# compashin_izzonu_fine.net
KiCad netlist of a schematic drawn in EAGLE
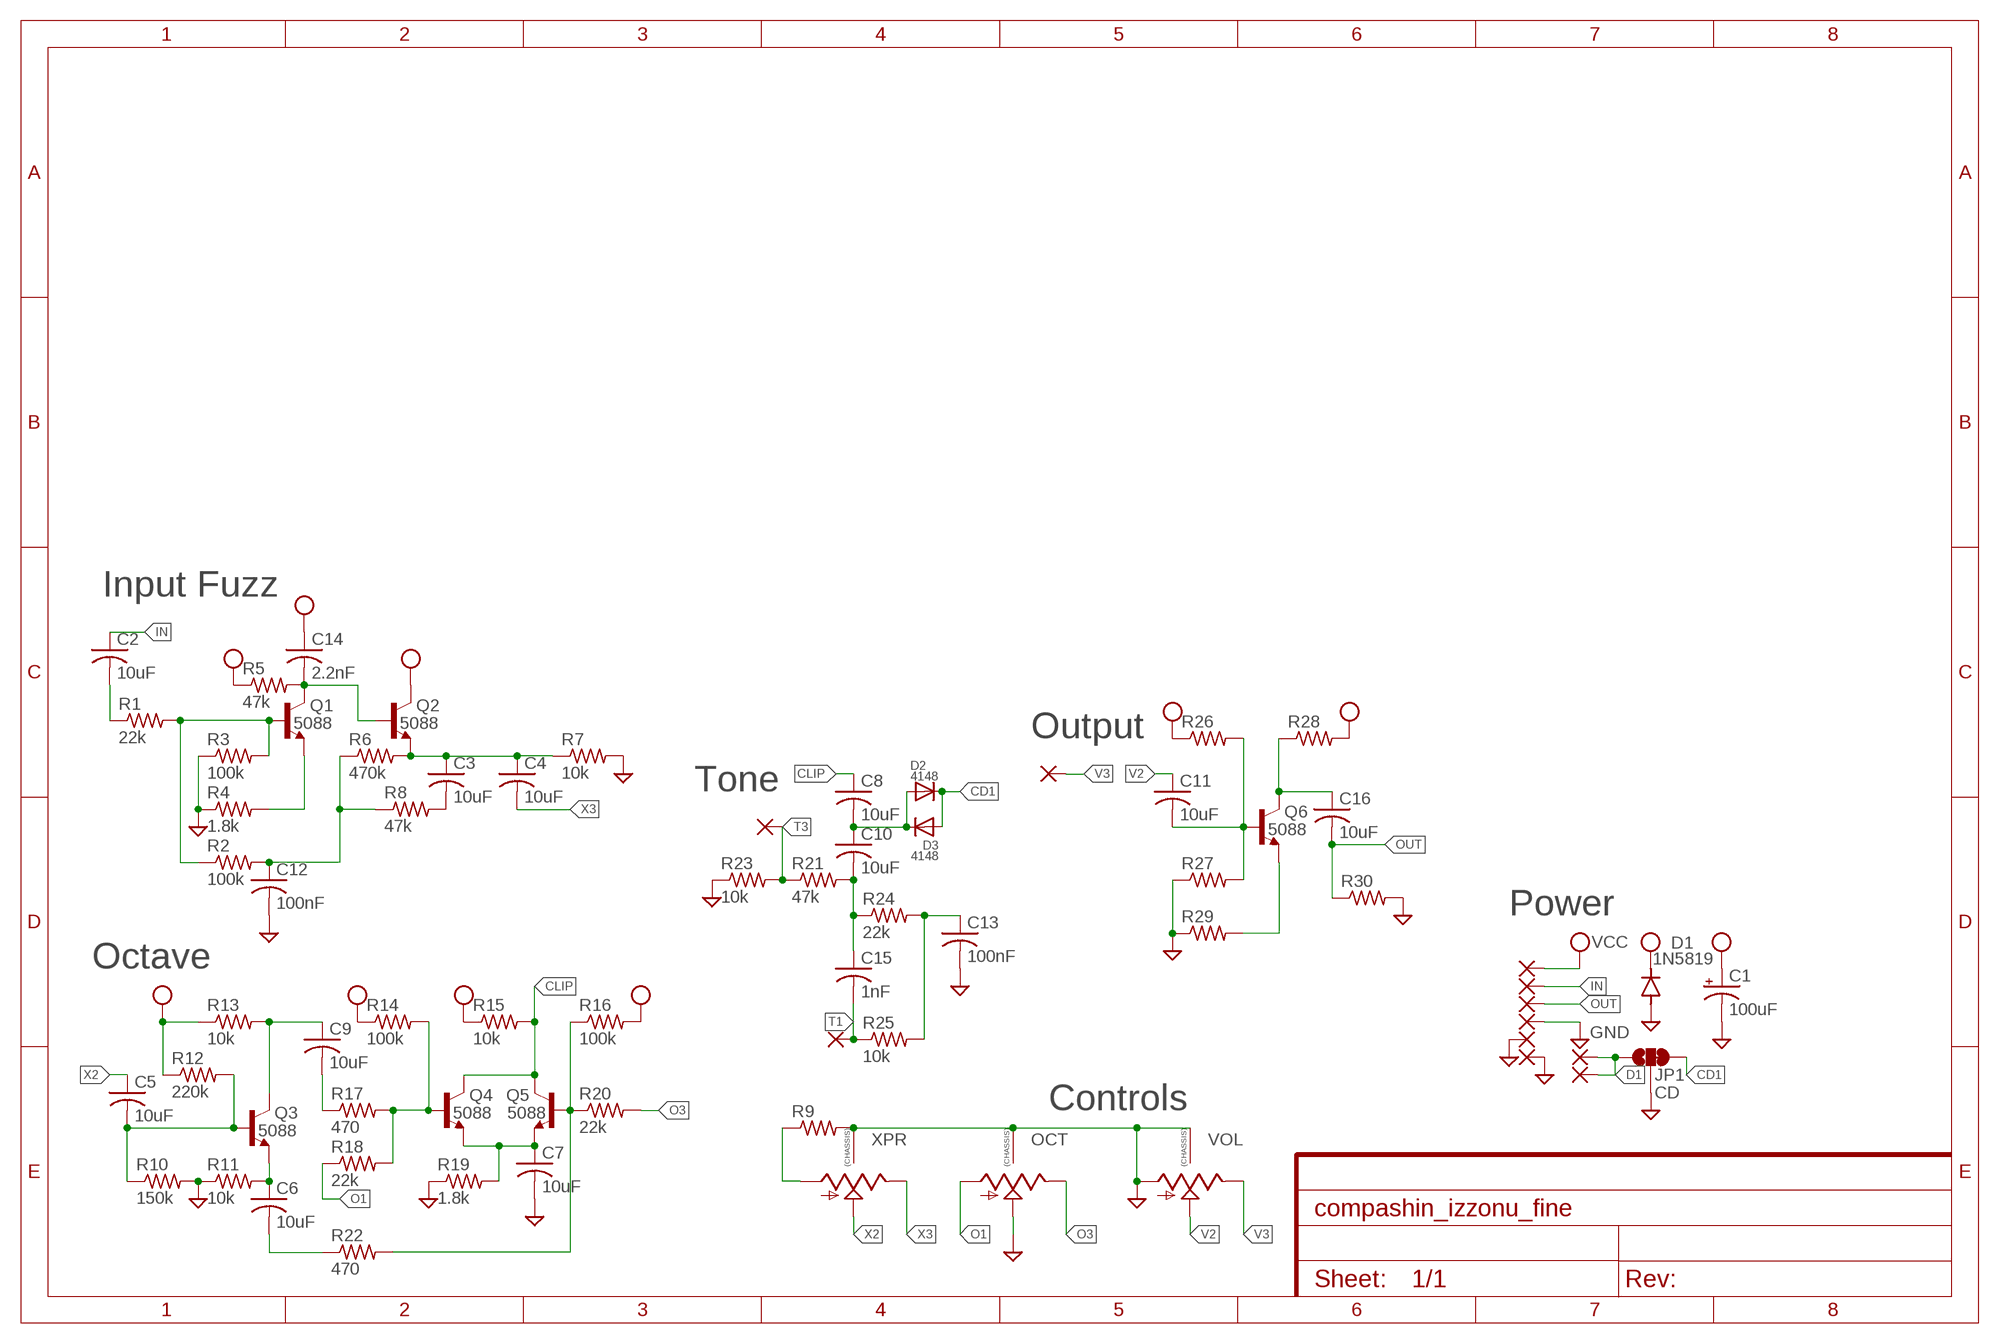
[diagram p0: schematic, sheet 1]

(export (version "E")
  (design (tool "Eeschema 10.0.6"))
  (components
    (comp (ref "C1")
      (value "100uF")
      (footprint "eagle-import:CPOL-RADIAL-2.5MM-6.5MM")
      (libsource (lib "eagle-import") (part "100UF-POLAR-RADIAL-2.5MM-25V-20%"))
    )
    (comp (ref "C2")
      (value "10uF")
      (footprint "eagle-import:C0805")
      (libsource (lib "eagle-import") (part "C-USC0805"))
    )
    (comp (ref "C3")
      (value "10uF")
      (footprint "eagle-import:C0805")
      (libsource (lib "eagle-import") (part "C-USC0805"))
    )
    (comp (ref "C4")
      (value "10uF")
      (footprint "eagle-import:C0805")
      (libsource (lib "eagle-import") (part "C-USC0805"))
    )
    (comp (ref "C5")
      (value "10uF")
      (footprint "eagle-import:C0805")
      (libsource (lib "eagle-import") (part "C-USC0805"))
    )
    (comp (ref "C6")
      (value "10uF")
      (footprint "eagle-import:C0805")
      (libsource (lib "eagle-import") (part "C-USC0805"))
    )
    (comp (ref "C7")
      (value "10uF")
      (footprint "eagle-import:C0805")
      (libsource (lib "eagle-import") (part "C-USC0805"))
    )
    (comp (ref "C8")
      (value "10uF")
      (footprint "eagle-import:C0805")
      (libsource (lib "eagle-import") (part "C-USC0805"))
    )
    (comp (ref "C9")
      (value "10uF")
      (footprint "eagle-import:C0805")
      (libsource (lib "eagle-import") (part "C-USC0805"))
    )
    (comp (ref "C10")
      (value "10uF")
      (footprint "eagle-import:C0805")
      (libsource (lib "eagle-import") (part "C-USC0805"))
    )
    (comp (ref "C11")
      (value "10uF")
      (footprint "eagle-import:C0805")
      (libsource (lib "eagle-import") (part "C-USC0805"))
    )
    (comp (ref "C12")
      (value "100nF")
      (footprint "eagle-import:C0402")
      (libsource (lib "eagle-import") (part "C-USC0402"))
    )
    (comp (ref "C13")
      (value "100nF")
      (footprint "eagle-import:C0402")
      (libsource (lib "eagle-import") (part "C-USC0402"))
    )
    (comp (ref "C14")
      (value "2.2nF")
      (footprint "eagle-import:C0402")
      (libsource (lib "eagle-import") (part "C-USC0402"))
    )
    (comp (ref "C15")
      (value "1nF")
      (footprint "eagle-import:C0402")
      (libsource (lib "eagle-import") (part "C-USC0402"))
    )
    (comp (ref "C16")
      (value "10uF")
      (footprint "eagle-import:C0805")
      (libsource (lib "eagle-import") (part "C-USC0805"))
    )
    (comp (ref "D1")
      (value "1N5819")
      (footprint "eagle-import:SOD123")
      (libsource (lib "eagle-import") (part "DIODE-SOD123"))
    )
    (comp (ref "D2")
      (value "4148")
      (footprint "eagle-import:SOD-123")
      (libsource (lib "eagle-import") (part "DIODESOD-123"))
    )
    (comp (ref "D3")
      (value "4148")
      (footprint "eagle-import:SOD-123")
      (libsource (lib "eagle-import") (part "DIODESOD-123"))
    )
    (comp (ref "JP1")
      (value "CD")
      (footprint "eagle-import:SMT-JUMPER_3_1-NC_TRACE_SILK")
      (libsource (lib "eagle-import") (part "JUMPER-SMT_3_1-NC_TRACE_SILK"))
    )
    (comp (ref "OCT")
      (value "9MM_SNAP-IN_POT_CHASSIS")
      (footprint "eagle-import:9MM_SNAP-IN_POT")
      (libsource (lib "eagle-import") (part "9MM_SNAP-IN_POT_CHASSIS"))
    )
    (comp (ref "PAD1")
      (value "1,6/0,8")
      (footprint "eagle-import:1,6_0,8")
      (libsource (lib "eagle-import") (part "1,6/0,8"))
    )
    (comp (ref "PAD2")
      (value "1,6/0,8")
      (footprint "eagle-import:1,6_0,8")
      (libsource (lib "eagle-import") (part "1,6/0,8"))
    )
    (comp (ref "PAD3")
      (value "1,6/0,8")
      (footprint "eagle-import:1,6_0,8")
      (libsource (lib "eagle-import") (part "1,6/0,8"))
    )
    (comp (ref "PAD4")
      (value "1,6/0,8")
      (footprint "eagle-import:1,6_0,8")
      (libsource (lib "eagle-import") (part "1,6/0,8"))
    )
    (comp (ref "PAD5")
      (value "1,6/0,8")
      (footprint "eagle-import:1,6_0,8")
      (libsource (lib "eagle-import") (part "1,6/0,8"))
    )
    (comp (ref "PAD6")
      (value "1,6/0,8")
      (footprint "eagle-import:1,6_0,8")
      (libsource (lib "eagle-import") (part "1,6/0,8"))
    )
    (comp (ref "PAD7")
      (value "1,6/0,8")
      (footprint "eagle-import:1,6_0,8")
      (libsource (lib "eagle-import") (part "1,6/0,8"))
    )
    (comp (ref "PAD8")
      (value "1,6/0,8")
      (footprint "eagle-import:1,6_0,8")
      (libsource (lib "eagle-import") (part "1,6/0,8"))
    )
    (comp (ref "Q1")
      (value "5088")
      (footprint "eagle-import:SOT23-BEC")
      (fields (field (name "MF") "ON Semiconductor") (field (name "MP") "MMBT5088"))
      (libsource (lib "eagle-import") (part "MMBT5088"))
    )
    (comp (ref "Q2")
      (value "5088")
      (footprint "eagle-import:SOT23-BEC")
      (fields (field (name "MF") "ON Semiconductor") (field (name "MP") "MMBT5088"))
      (libsource (lib "eagle-import") (part "MMBT5088"))
    )
    (comp (ref "Q3")
      (value "5088")
      (footprint "eagle-import:SOT23-BEC")
      (fields (field (name "MF") "ON Semiconductor") (field (name "MP") "MMBT5088"))
      (libsource (lib "eagle-import") (part "MMBT5088"))
    )
    (comp (ref "Q4")
      (value "5088")
      (footprint "eagle-import:SOT23-BEC")
      (fields (field (name "MF") "ON Semiconductor") (field (name "MP") "MMBT5088"))
      (libsource (lib "eagle-import") (part "MMBT5088"))
    )
    (comp (ref "Q5")
      (value "5088")
      (footprint "eagle-import:SOT23-BEC")
      (fields (field (name "MF") "ON Semiconductor") (field (name "MP") "MMBT5088"))
      (libsource (lib "eagle-import") (part "MMBT5088"))
    )
    (comp (ref "Q6")
      (value "5088")
      (footprint "eagle-import:SOT23-BEC")
      (fields (field (name "MF") "ON Semiconductor") (field (name "MP") "MMBT5088"))
      (libsource (lib "eagle-import") (part "MMBT5088"))
    )
    (comp (ref "R1")
      (value "22k")
      (footprint "eagle-import:R0402")
      (libsource (lib "eagle-import") (part "R-US_R0402"))
    )
    (comp (ref "R2")
      (value "100k")
      (footprint "eagle-import:R0402")
      (libsource (lib "eagle-import") (part "R-US_R0402"))
    )
    (comp (ref "R3")
      (value "100k")
      (footprint "eagle-import:R0402")
      (libsource (lib "eagle-import") (part "R-US_R0402"))
    )
    (comp (ref "R4")
      (value "1.8k")
      (footprint "eagle-import:R0402")
      (libsource (lib "eagle-import") (part "R-US_R0402"))
    )
    (comp (ref "R5")
      (value "47k")
      (footprint "eagle-import:R0402")
      (libsource (lib "eagle-import") (part "R-US_R0402"))
    )
    (comp (ref "R6")
      (value "470k")
      (footprint "eagle-import:R0402")
      (libsource (lib "eagle-import") (part "R-US_R0402"))
    )
    (comp (ref "R7")
      (value "10k")
      (footprint "eagle-import:R0402")
      (libsource (lib "eagle-import") (part "R-US_R0402"))
    )
    (comp (ref "R8")
      (value "47k")
      (footprint "eagle-import:R0402")
      (libsource (lib "eagle-import") (part "R-US_R0402"))
    )
    (comp (ref "R9")
      (value "R-US_R0402")
      (footprint "eagle-import:R0402")
      (libsource (lib "eagle-import") (part "R-US_R0402"))
    )
    (comp (ref "R10")
      (value "150k")
      (footprint "eagle-import:R0402")
      (libsource (lib "eagle-import") (part "R-US_R0402"))
    )
    (comp (ref "R11")
      (value "10k")
      (footprint "eagle-import:R0402")
      (libsource (lib "eagle-import") (part "R-US_R0402"))
    )
    (comp (ref "R12")
      (value "220k")
      (footprint "eagle-import:R0402")
      (libsource (lib "eagle-import") (part "R-US_R0402"))
    )
    (comp (ref "R13")
      (value "10k")
      (footprint "eagle-import:R0402")
      (libsource (lib "eagle-import") (part "R-US_R0402"))
    )
    (comp (ref "R14")
      (value "100k")
      (footprint "eagle-import:R0402")
      (libsource (lib "eagle-import") (part "R-US_R0402"))
    )
    (comp (ref "R15")
      (value "10k")
      (footprint "eagle-import:R0402")
      (libsource (lib "eagle-import") (part "R-US_R0402"))
    )
    (comp (ref "R16")
      (value "100k")
      (footprint "eagle-import:R0402")
      (libsource (lib "eagle-import") (part "R-US_R0402"))
    )
    (comp (ref "R17")
      (value "470")
      (footprint "eagle-import:R0402")
      (libsource (lib "eagle-import") (part "R-US_R0402"))
    )
    (comp (ref "R18")
      (value "22k")
      (footprint "eagle-import:R0402")
      (libsource (lib "eagle-import") (part "R-US_R0402"))
    )
    (comp (ref "R19")
      (value "1.8k")
      (footprint "eagle-import:R0402")
      (libsource (lib "eagle-import") (part "R-US_R0402"))
    )
    (comp (ref "R20")
      (value "22k")
      (footprint "eagle-import:R0402")
      (libsource (lib "eagle-import") (part "R-US_R0402"))
    )
    (comp (ref "R21")
      (value "47k")
      (footprint "eagle-import:R0402")
      (libsource (lib "eagle-import") (part "R-US_R0402"))
    )
    (comp (ref "R22")
      (value "470")
      (footprint "eagle-import:R0402")
      (libsource (lib "eagle-import") (part "R-US_R0402"))
    )
    (comp (ref "R23")
      (value "10k")
      (footprint "eagle-import:R0402")
      (libsource (lib "eagle-import") (part "R-US_R0402"))
    )
    (comp (ref "R24")
      (value "22k")
      (footprint "eagle-import:R0402")
      (libsource (lib "eagle-import") (part "R-US_R0402"))
    )
    (comp (ref "R25")
      (value "10k")
      (footprint "eagle-import:R0402")
      (libsource (lib "eagle-import") (part "R-US_R0402"))
    )
    (comp (ref "R26")
      (value "R-US_R0402")
      (footprint "eagle-import:R0402")
      (libsource (lib "eagle-import") (part "R-US_R0402"))
    )
    (comp (ref "R27")
      (value "R-US_R0402")
      (footprint "eagle-import:R0402")
      (libsource (lib "eagle-import") (part "R-US_R0402"))
    )
    (comp (ref "R28")
      (value "R-US_R0402")
      (footprint "eagle-import:R0402")
      (libsource (lib "eagle-import") (part "R-US_R0402"))
    )
    (comp (ref "R29")
      (value "R-US_R0402")
      (footprint "eagle-import:R0402")
      (libsource (lib "eagle-import") (part "R-US_R0402"))
    )
    (comp (ref "R30")
      (value "R-US_R0402")
      (footprint "eagle-import:R0402")
      (libsource (lib "eagle-import") (part "R-US_R0402"))
    )
    (comp (ref "T1")
      (value "1,6/0,8")
      (footprint "eagle-import:1,6_0,8")
      (libsource (lib "eagle-import") (part "1,6/0,8"))
    )
    (comp (ref "T2")
      (value "1,6/0,8")
      (footprint "eagle-import:1,6_0,8")
      (libsource (lib "eagle-import") (part "1,6/0,8"))
    )
    (comp (ref "T3")
      (value "1,6/0,8")
      (footprint "eagle-import:1,6_0,8")
      (libsource (lib "eagle-import") (part "1,6/0,8"))
    )
    (comp (ref "VOL")
      (value "9MM_SNAP-IN_POT_CHASSIS")
      (footprint "eagle-import:9MM_SNAP-IN_POT")
      (libsource (lib "eagle-import") (part "9MM_SNAP-IN_POT_CHASSIS"))
    )
    (comp (ref "XPR")
      (value "9MM_SNAP-IN_POT_CHASSIS")
      (footprint "eagle-import:9MM_SNAP-IN_POT")
      (libsource (lib "eagle-import") (part "9MM_SNAP-IN_POT_CHASSIS"))
    )
  )
  (nets
    (net (code "1") (name "CD1") (class "Default")
      (node (ref "D2") (pin "C") (pinfunction "C_C") (pintype "passive"))
      (node (ref "D3") (pin "A") (pinfunction "A_A") (pintype "passive"))
      (node (ref "JP1") (pin "3") (pinfunction "3_3") (pintype "passive"))
    )
    (net (code "2") (name "CLIP") (class "Default")
      (node (ref "C8") (pin "1") (pinfunction "1_1") (pintype "passive"))
      (node (ref "Q4") (pin "C") (pinfunction "C_C") (pintype "passive"))
      (node (ref "Q5") (pin "C") (pinfunction "C_C") (pintype "passive"))
      (node (ref "R15") (pin "2") (pinfunction "2_2") (pintype "passive"))
    )
    (net (code "3") (name "D1") (class "Default")
      (node (ref "JP1") (pin "1") (pinfunction "1_1") (pintype "passive"))
      (node (ref "PAD7") (pin "1") (pinfunction "P_1") (pintype "passive"))
      (node (ref "PAD8") (pin "1") (pinfunction "P_1") (pintype "passive"))
    )
    (net (code "4") (name "GND") (class "Default")
      (node (ref "C1") (pin "2") (pinfunction "-_2") (pintype "passive"))
      (node (ref "C12") (pin "2") (pinfunction "2_2") (pintype "passive"))
      (node (ref "C13") (pin "2") (pinfunction "2_2") (pintype "passive"))
      (node (ref "C7") (pin "2") (pinfunction "2_2") (pintype "passive"))
      (node (ref "D1") (pin "A") (pinfunction "A_A") (pintype "passive"))
      (node (ref "JP1") (pin "2") (pinfunction "2_2") (pintype "passive"))
      (node (ref "OCT") (pin "2") (pinfunction "S_2") (pintype "passive"))
      (node (ref "OCT") (pin "CHASSIS1") (pinfunction "P$1_CHASSIS1") (pintype "passive"))
      (node (ref "OCT") (pin "CHASSIS2") (pinfunction "P$1_CHASSIS2") (pintype "passive"))
      (node (ref "PAD4") (pin "1") (pinfunction "P_1") (pintype "passive"))
      (node (ref "PAD5") (pin "1") (pinfunction "P_1") (pintype "passive"))
      (node (ref "PAD6") (pin "1") (pinfunction "P_1") (pintype "passive"))
      (node (ref "R10") (pin "2") (pinfunction "2_2") (pintype "passive"))
      (node (ref "R11") (pin "1") (pinfunction "1_1") (pintype "passive"))
      (node (ref "R19") (pin "1") (pinfunction "1_1") (pintype "passive"))
      (node (ref "R23") (pin "1") (pinfunction "1_1") (pintype "passive"))
      (node (ref "R27") (pin "1") (pinfunction "1_1") (pintype "passive"))
      (node (ref "R29") (pin "1") (pinfunction "1_1") (pintype "passive"))
      (node (ref "R3") (pin "1") (pinfunction "1_1") (pintype "passive"))
      (node (ref "R30") (pin "2") (pinfunction "2_2") (pintype "passive"))
      (node (ref "R4") (pin "1") (pinfunction "1_1") (pintype "passive"))
      (node (ref "R7") (pin "2") (pinfunction "2_2") (pintype "passive"))
      (node (ref "R9") (pin "2") (pinfunction "2_2") (pintype "passive"))
      (node (ref "VOL") (pin "1") (pinfunction "A_1") (pintype "passive"))
      (node (ref "VOL") (pin "CHASSIS1") (pinfunction "P$1_CHASSIS1") (pintype "passive"))
      (node (ref "VOL") (pin "CHASSIS2") (pinfunction "P$1_CHASSIS2") (pintype "passive"))
      (node (ref "XPR") (pin "CHASSIS1") (pinfunction "P$1_CHASSIS1") (pintype "passive"))
      (node (ref "XPR") (pin "CHASSIS2") (pinfunction "P$1_CHASSIS2") (pintype "passive"))
    )
    (net (code "5") (name "IN") (class "Default")
      (node (ref "C2") (pin "1") (pinfunction "1_1") (pintype "passive"))
      (node (ref "PAD2") (pin "1") (pinfunction "P_1") (pintype "passive"))
    )
    (net (code "6") (name "Net-(C2-Pad2)") (class "Default")
      (node (ref "C2") (pin "2") (pinfunction "2_2") (pintype "passive"))
      (node (ref "R1") (pin "1") (pinfunction "1_1") (pintype "passive"))
    )
    (net (code "7") (name "Net-(C3-Pad1)") (class "Default")
      (node (ref "C3") (pin "1") (pinfunction "1_1") (pintype "passive"))
      (node (ref "C4") (pin "1") (pinfunction "1_1") (pintype "passive"))
      (node (ref "Q2") (pin "E") (pinfunction "E_E") (pintype "passive"))
      (node (ref "R6") (pin "2") (pinfunction "2_2") (pintype "passive"))
      (node (ref "R7") (pin "1") (pinfunction "1_1") (pintype "passive"))
    )
    (net (code "8") (name "Net-(C3-Pad2)") (class "Default")
      (node (ref "C3") (pin "2") (pinfunction "2_2") (pintype "passive"))
      (node (ref "R8") (pin "2") (pinfunction "2_2") (pintype "passive"))
    )
    (net (code "9") (name "Net-(C5-Pad2)") (class "Default")
      (node (ref "C5") (pin "2") (pinfunction "2_2") (pintype "passive"))
      (node (ref "Q3") (pin "B") (pinfunction "B_B") (pintype "passive"))
      (node (ref "R10") (pin "1") (pinfunction "1_1") (pintype "passive"))
      (node (ref "R12") (pin "2") (pinfunction "2_2") (pintype "passive"))
    )
    (net (code "10") (name "Net-(C6-Pad1)") (class "Default")
      (node (ref "C6") (pin "1") (pinfunction "1_1") (pintype "passive"))
      (node (ref "Q3") (pin "E") (pinfunction "E_E") (pintype "passive"))
      (node (ref "R11") (pin "2") (pinfunction "2_2") (pintype "passive"))
    )
    (net (code "11") (name "Net-(C6-Pad2)") (class "Default")
      (node (ref "C6") (pin "2") (pinfunction "2_2") (pintype "passive"))
      (node (ref "R22") (pin "1") (pinfunction "1_1") (pintype "passive"))
    )
    (net (code "12") (name "Net-(C7-Pad1)") (class "Default")
      (node (ref "C7") (pin "1") (pinfunction "1_1") (pintype "passive"))
      (node (ref "Q4") (pin "E") (pinfunction "E_E") (pintype "passive"))
      (node (ref "Q5") (pin "E") (pinfunction "E_E") (pintype "passive"))
      (node (ref "R19") (pin "2") (pinfunction "2_2") (pintype "passive"))
    )
    (net (code "13") (name "Net-(C9-Pad1)") (class "Default")
      (node (ref "C9") (pin "1") (pinfunction "1_1") (pintype "passive"))
      (node (ref "Q3") (pin "C") (pinfunction "C_C") (pintype "passive"))
      (node (ref "R13") (pin "2") (pinfunction "2_2") (pintype "passive"))
    )
    (net (code "14") (name "Net-(C9-Pad2)") (class "Default")
      (node (ref "C9") (pin "2") (pinfunction "2_2") (pintype "passive"))
      (node (ref "R17") (pin "1") (pinfunction "1_1") (pintype "passive"))
    )
    (net (code "15") (name "Net-(C10-Pad1)") (class "Default")
      (node (ref "C10") (pin "1") (pinfunction "1_1") (pintype "passive"))
      (node (ref "C8") (pin "2") (pinfunction "2_2") (pintype "passive"))
      (node (ref "D2") (pin "A") (pinfunction "A_A") (pintype "passive"))
      (node (ref "D3") (pin "C") (pinfunction "C_C") (pintype "passive"))
    )
    (net (code "16") (name "Net-(C10-Pad2)") (class "Default")
      (node (ref "C10") (pin "2") (pinfunction "2_2") (pintype "passive"))
      (node (ref "C15") (pin "1") (pinfunction "1_1") (pintype "passive"))
      (node (ref "R21") (pin "2") (pinfunction "2_2") (pintype "passive"))
      (node (ref "R24") (pin "1") (pinfunction "1_1") (pintype "passive"))
    )
    (net (code "17") (name "Net-(C11-Pad2)") (class "Default")
      (node (ref "C11") (pin "2") (pinfunction "2_2") (pintype "passive"))
      (node (ref "Q6") (pin "B") (pinfunction "B_B") (pintype "passive"))
      (node (ref "R26") (pin "2") (pinfunction "2_2") (pintype "passive"))
      (node (ref "R27") (pin "2") (pinfunction "2_2") (pintype "passive"))
    )
    (net (code "18") (name "Net-(C12-Pad1)") (class "Default")
      (node (ref "C12") (pin "1") (pinfunction "1_1") (pintype "passive"))
      (node (ref "R2") (pin "2") (pinfunction "2_2") (pintype "passive"))
      (node (ref "R6") (pin "1") (pinfunction "1_1") (pintype "passive"))
      (node (ref "R8") (pin "1") (pinfunction "1_1") (pintype "passive"))
    )
    (net (code "19") (name "Net-(C13-Pad1)") (class "Default")
      (node (ref "C13") (pin "1") (pinfunction "1_1") (pintype "passive"))
      (node (ref "R24") (pin "2") (pinfunction "2_2") (pintype "passive"))
      (node (ref "R25") (pin "2") (pinfunction "2_2") (pintype "passive"))
    )
    (net (code "20") (name "Net-(C14-Pad2)") (class "Default")
      (node (ref "C14") (pin "2") (pinfunction "2_2") (pintype "passive"))
      (node (ref "Q1") (pin "C") (pinfunction "C_C") (pintype "passive"))
      (node (ref "Q2") (pin "B") (pinfunction "B_B") (pintype "passive"))
      (node (ref "R5") (pin "2") (pinfunction "2_2") (pintype "passive"))
    )
    (net (code "21") (name "Net-(C16-Pad1)") (class "Default")
      (node (ref "C16") (pin "1") (pinfunction "1_1") (pintype "passive"))
      (node (ref "Q6") (pin "C") (pinfunction "C_C") (pintype "passive"))
      (node (ref "R28") (pin "1") (pinfunction "1_1") (pintype "passive"))
    )
    (net (code "22") (name "Net-(Q1-PadB)") (class "Default")
      (node (ref "Q1") (pin "B") (pinfunction "B_B") (pintype "passive"))
      (node (ref "R1") (pin "2") (pinfunction "2_2") (pintype "passive"))
      (node (ref "R2") (pin "1") (pinfunction "1_1") (pintype "passive"))
      (node (ref "R3") (pin "2") (pinfunction "2_2") (pintype "passive"))
    )
    (net (code "23") (name "Net-(Q1-PadE)") (class "Default")
      (node (ref "Q1") (pin "E") (pinfunction "E_E") (pintype "passive"))
      (node (ref "R4") (pin "2") (pinfunction "2_2") (pintype "passive"))
    )
    (net (code "24") (name "Net-(Q4-PadB)") (class "Default")
      (node (ref "Q4") (pin "B") (pinfunction "B_B") (pintype "passive"))
      (node (ref "R14") (pin "2") (pinfunction "2_2") (pintype "passive"))
      (node (ref "R17") (pin "2") (pinfunction "2_2") (pintype "passive"))
      (node (ref "R18") (pin "2") (pinfunction "2_2") (pintype "passive"))
    )
    (net (code "25") (name "Net-(Q5-PadB)") (class "Default")
      (node (ref "Q5") (pin "B") (pinfunction "B_B") (pintype "passive"))
      (node (ref "R16") (pin "1") (pinfunction "1_1") (pintype "passive"))
      (node (ref "R20") (pin "1") (pinfunction "1_1") (pintype "passive"))
      (node (ref "R22") (pin "2") (pinfunction "2_2") (pintype "passive"))
    )
    (net (code "26") (name "Net-(Q6-PadE)") (class "Default")
      (node (ref "Q6") (pin "E") (pinfunction "E_E") (pintype "passive"))
      (node (ref "R29") (pin "2") (pinfunction "2_2") (pintype "passive"))
    )
    (net (code "27") (name "Net-(XPR-A)") (class "Default")
      (node (ref "R9") (pin "1") (pinfunction "1_1") (pintype "passive"))
      (node (ref "XPR") (pin "1") (pinfunction "A_1") (pintype "passive"))
    )
    (net (code "28") (name "O1") (class "Default")
      (node (ref "OCT") (pin "1") (pinfunction "A_1") (pintype "passive"))
      (node (ref "R18") (pin "1") (pinfunction "1_1") (pintype "passive"))
    )
    (net (code "29") (name "O3") (class "Default")
      (node (ref "OCT") (pin "3") (pinfunction "E_3") (pintype "passive"))
      (node (ref "R20") (pin "2") (pinfunction "2_2") (pintype "passive"))
    )
    (net (code "30") (name "OUT") (class "Default")
      (node (ref "C16") (pin "2") (pinfunction "2_2") (pintype "passive"))
      (node (ref "PAD3") (pin "1") (pinfunction "P_1") (pintype "passive"))
      (node (ref "R30") (pin "1") (pinfunction "1_1") (pintype "passive"))
    )
    (net (code "31") (name "T1") (class "Default")
      (node (ref "C15") (pin "2") (pinfunction "2_2") (pintype "passive"))
      (node (ref "R25") (pin "1") (pinfunction "1_1") (pintype "passive"))
      (node (ref "T1") (pin "1") (pinfunction "P_1") (pintype "passive"))
    )
    (net (code "32") (name "T3") (class "Default")
      (node (ref "R21") (pin "1") (pinfunction "1_1") (pintype "passive"))
      (node (ref "R23") (pin "2") (pinfunction "2_2") (pintype "passive"))
      (node (ref "T3") (pin "1") (pinfunction "P_1") (pintype "passive"))
    )
    (net (code "33") (name "V2") (class "Default")
      (node (ref "C11") (pin "1") (pinfunction "1_1") (pintype "passive"))
      (node (ref "VOL") (pin "2") (pinfunction "S_2") (pintype "passive"))
    )
    (net (code "34") (name "V3") (class "Default")
      (node (ref "T2") (pin "1") (pinfunction "P_1") (pintype "passive"))
      (node (ref "VOL") (pin "3") (pinfunction "E_3") (pintype "passive"))
    )
    (net (code "35") (name "VCC") (class "Default")
      (node (ref "C1") (pin "1") (pinfunction "+_1") (pintype "passive"))
      (node (ref "C14") (pin "1") (pinfunction "1_1") (pintype "passive"))
      (node (ref "D1") (pin "C") (pinfunction "C_C") (pintype "passive"))
      (node (ref "PAD1") (pin "1") (pinfunction "P_1") (pintype "passive"))
      (node (ref "Q2") (pin "C") (pinfunction "C_C") (pintype "passive"))
      (node (ref "R12") (pin "1") (pinfunction "1_1") (pintype "passive"))
      (node (ref "R13") (pin "1") (pinfunction "1_1") (pintype "passive"))
      (node (ref "R14") (pin "1") (pinfunction "1_1") (pintype "passive"))
      (node (ref "R15") (pin "1") (pinfunction "1_1") (pintype "passive"))
      (node (ref "R16") (pin "2") (pinfunction "2_2") (pintype "passive"))
      (node (ref "R26") (pin "1") (pinfunction "1_1") (pintype "passive"))
      (node (ref "R28") (pin "2") (pinfunction "2_2") (pintype "passive"))
      (node (ref "R5") (pin "1") (pinfunction "1_1") (pintype "passive"))
    )
    (net (code "36") (name "X2") (class "Default")
      (node (ref "C5") (pin "1") (pinfunction "1_1") (pintype "passive"))
      (node (ref "XPR") (pin "2") (pinfunction "S_2") (pintype "passive"))
    )
    (net (code "37") (name "X3") (class "Default")
      (node (ref "C4") (pin "2") (pinfunction "2_2") (pintype "passive"))
      (node (ref "XPR") (pin "3") (pinfunction "E_3") (pintype "passive"))
    )
  )
)
